# REUN_468349_001_PSU_Board_Power.net
KiCad netlist of a schematic drawn in Altium Designer
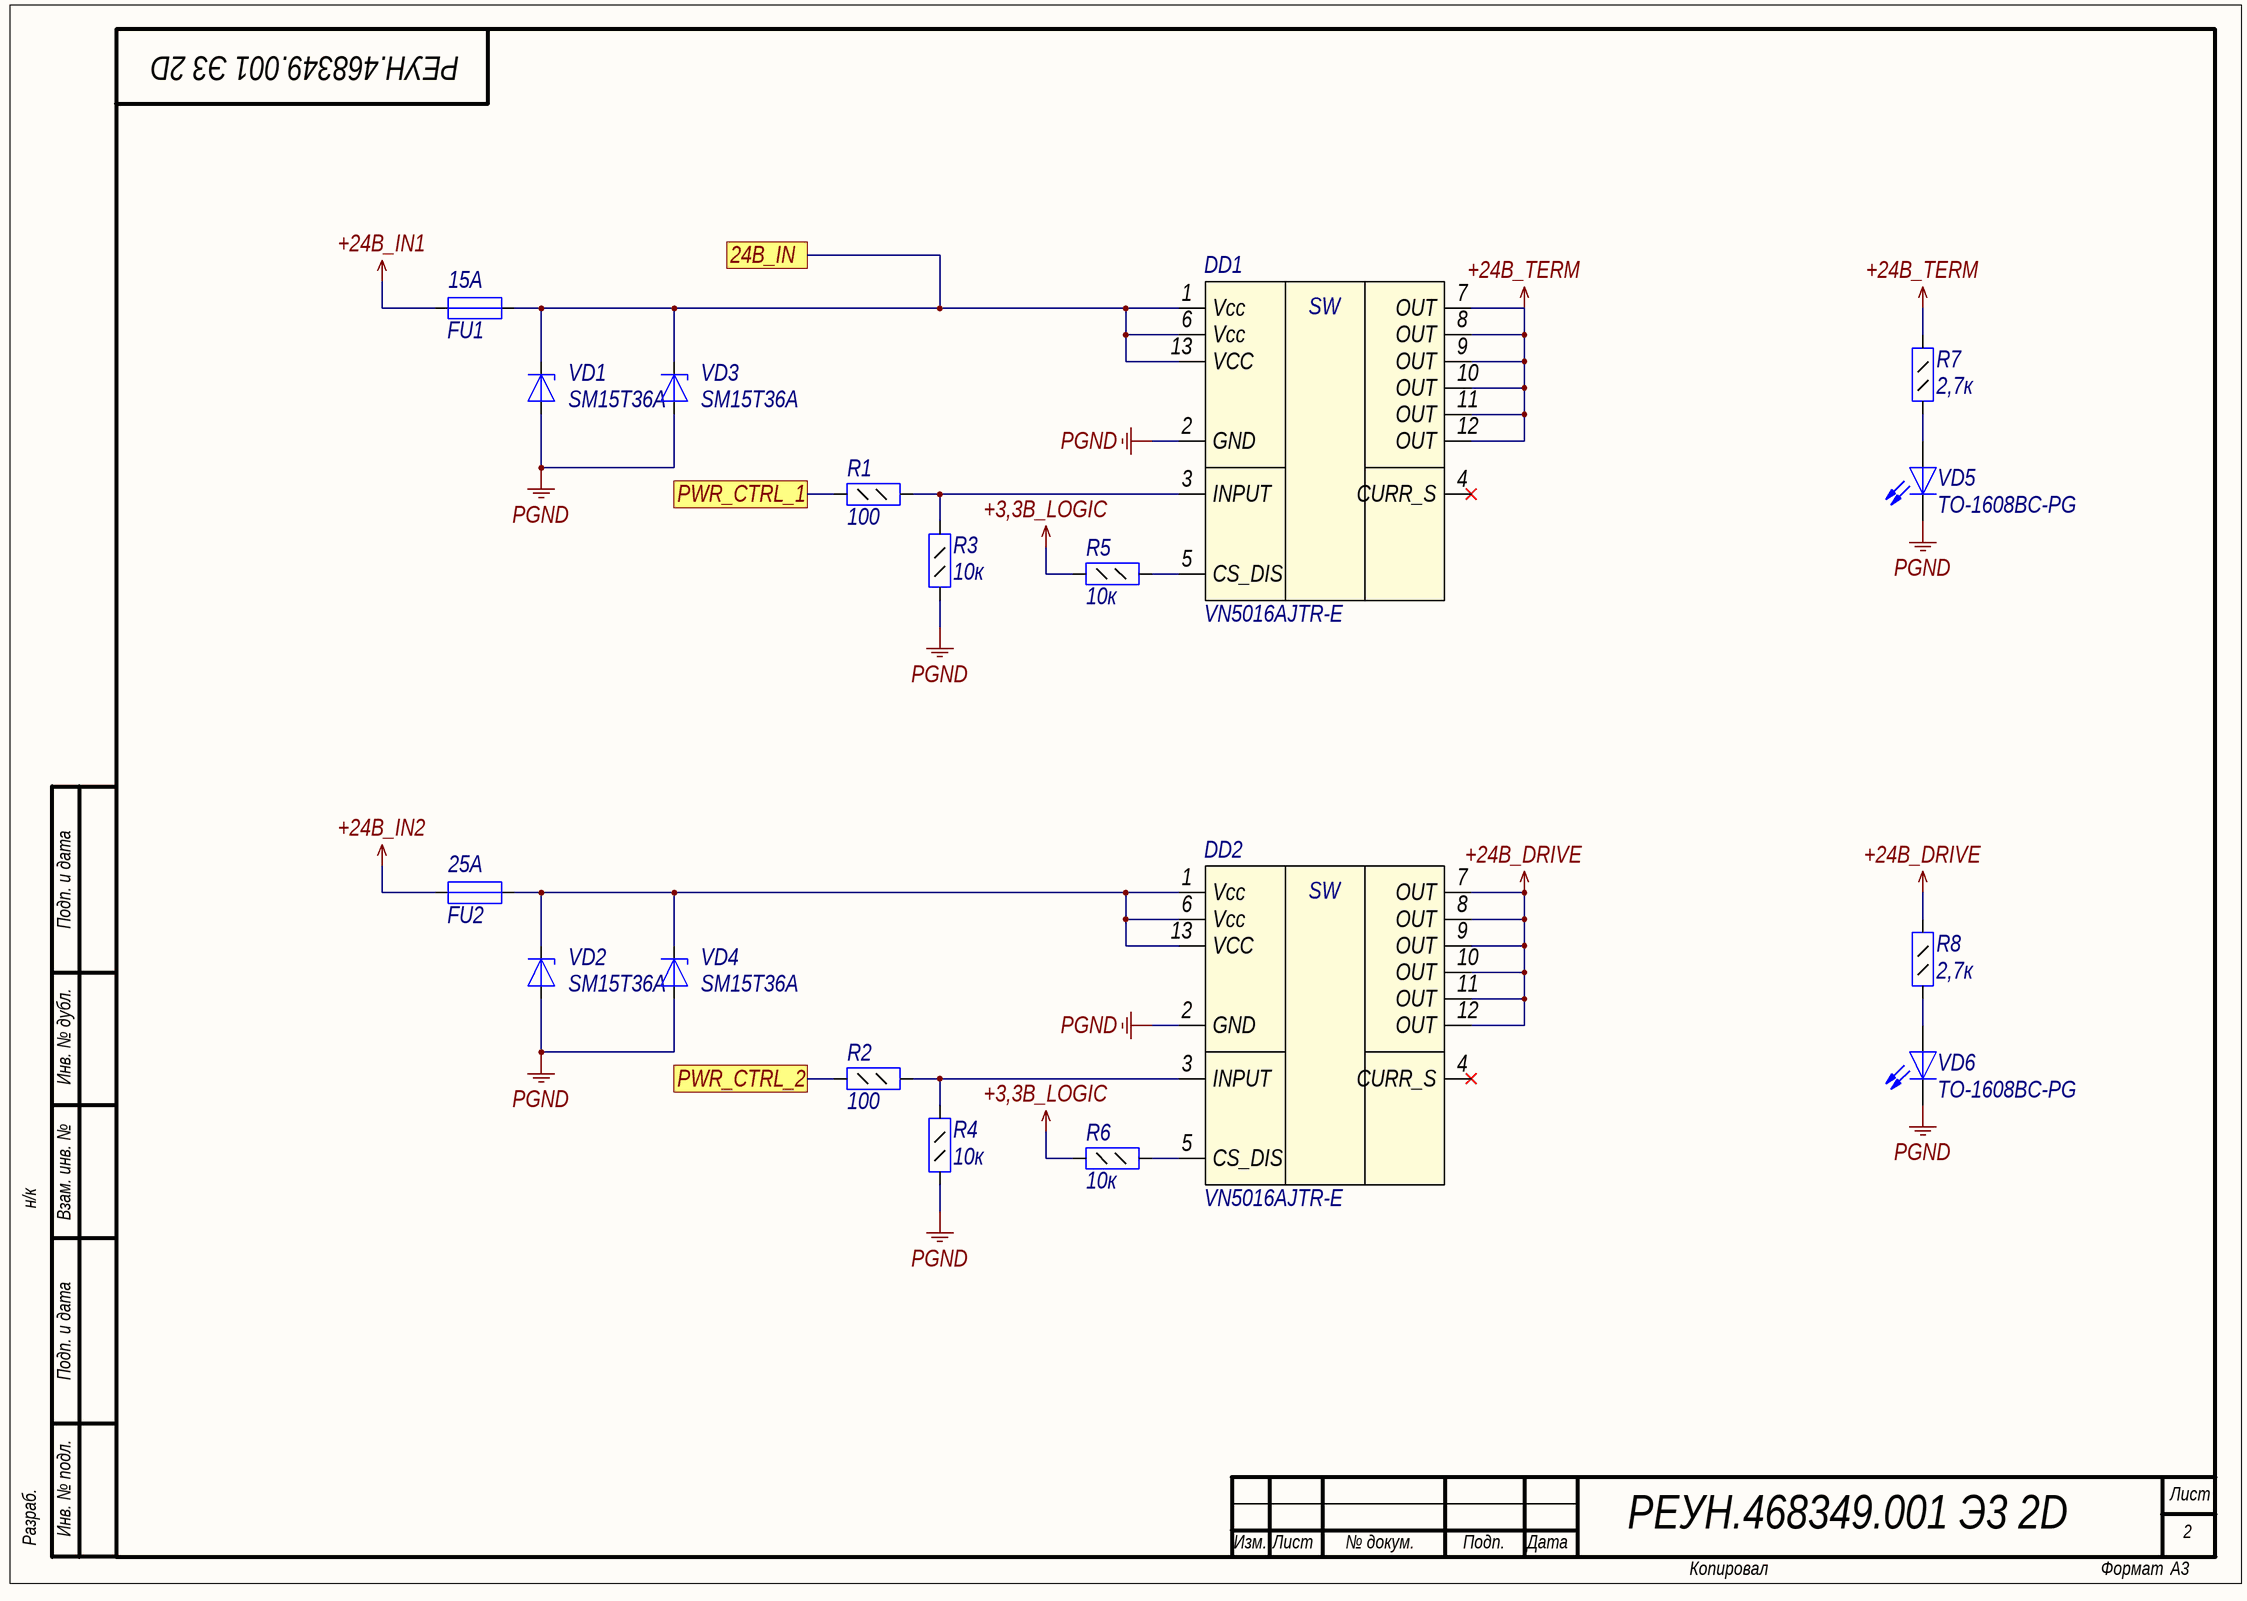
[diagram p0: REUN.468349.001_PSU_Board_Power.SchDoc]

(export (version "E")
  (design (tool "Eeschema 10.0.6"))
  (components
    (comp (ref "DD1")
      (value "VN5016AJTR-E")
      (footprint "POWERSO12")
      (description "Single channel high side driver with analog\r\ncurrent sense for automotive applications")
      (fields (field (name "MANUFACTURER") "STMicroelectronics"))
      (libsource (lib "REUN.468349.001_PSU_Board") (part "pwrsw5"))
    )
    (comp (ref "DD2")
      (value "VN5016AJTR-E")
      (footprint "POWERSO12")
      (description "Single channel high side driver with analog\r\ncurrent sense for automotive applications")
      (fields (field (name "MANUFACTURER") "STMicroelectronics"))
      (libsource (lib "REUN.468349.001_PSU_Board") (part "pwrsw5"))
    )
    (comp (ref "FU1")
      (value "Fuse")
      (footprint "F6.3x32")
      (description "Предохранитель")
      (fields (field (name "I MAX") "15А") (field (name "PART NUMBER") "189000.15"))
      (libsource (lib "MOP44") (part "Fuse"))
    )
    (comp (ref "FU2")
      (value "Fuse")
      (footprint "F6.3x30")
      (description "Предохранитель")
      (fields (field (name "I MAX") "25A") (field (name "PART NUMBER") "KLS5-1046-25000"))
      (libsource (lib "MOP44") (part "Fuse"))
    )
    (comp (ref "R1")
      (value "100")
      (footprint "R0805")
      (description "Резистор")
      (fields (field (name "PART NUMBER") "RC0805FR-07100RL") (field (name "POWER") "0,125Вт"))
      (libsource (lib "") (part "Resistor_0,125Вт_1"))
    )
    (comp (ref "R2")
      (value "100")
      (footprint "R0805")
      (description "Резистор")
      (fields (field (name "PART NUMBER") "RC0805FR-07100RL") (field (name "POWER") "0,125Вт"))
      (libsource (lib "") (part "Resistor_0,125Вт_1"))
    )
    (comp (ref "R3")
      (value "10к")
      (footprint "R0805")
      (description "Резистор")
      (fields (field (name "PART NUMBER") "RC0805FR-0710KL") (field (name "POWER") "0,125Вт"))
      (libsource (lib "MOP44") (part "Resistor_0,125Вт"))
    )
    (comp (ref "R4")
      (value "10к")
      (footprint "R0805")
      (description "Резистор")
      (fields (field (name "PART NUMBER") "RC0805FR-0710KL") (field (name "POWER") "0,125Вт"))
      (libsource (lib "MOP44") (part "Resistor_0,125Вт"))
    )
    (comp (ref "R5")
      (value "10к")
      (footprint "R0805")
      (description "Резистор")
      (fields (field (name "PART NUMBER") "RC0805FR-0710KL") (field (name "POWER") "0,125Вт"))
      (libsource (lib "") (part "Resistor_0,125Вт_1"))
    )
    (comp (ref "R6")
      (value "10к")
      (footprint "R0805")
      (description "Резистор")
      (fields (field (name "PART NUMBER") "RC0805FR-0710KL") (field (name "POWER") "0,125Вт"))
      (libsource (lib "") (part "Resistor_0,125Вт_1"))
    )
    (comp (ref "R7")
      (value "2,7к")
      (footprint "R0805")
      (description "Резистор")
      (fields (field (name "PART NUMBER") "RC0805FR-072K7") (field (name "POWER") "0,125Вт"))
      (libsource (lib "MOP44") (part "Resistor_0,125Вт"))
    )
    (comp (ref "R8")
      (value "2,7к")
      (footprint "R0805")
      (description "Резистор")
      (fields (field (name "PART NUMBER") "RC0805FR-072K7") (field (name "POWER") "0,125Вт"))
      (libsource (lib "MOP44") (part "Resistor_0,125Вт"))
    )
    (comp (ref "VD1")
      (value "SM15T36A")
      (footprint "SMC")
      (description "Cтабилитрон (лавинный выпрямительный диод) односторонний")
      (libsource (lib "MOP44") (part "DiodeZener"))
    )
    (comp (ref "VD2")
      (value "SM15T36A")
      (footprint "SMC")
      (description "Cтабилитрон (лавинный выпрямительный диод) односторонний")
      (libsource (lib "MOP44") (part "DiodeZener"))
    )
    (comp (ref "VD3")
      (value "SM15T36A")
      (footprint "SMC")
      (description "Cтабилитрон (лавинный выпрямительный диод) односторонний")
      (libsource (lib "MOP44") (part "DiodeZener"))
    )
    (comp (ref "VD4")
      (value "SM15T36A")
      (footprint "SMC")
      (description "Cтабилитрон (лавинный выпрямительный диод) односторонний")
      (libsource (lib "MOP44") (part "DiodeZener"))
    )
    (comp (ref "VD5")
      (value "TO-1608BC-PG")
      (footprint "L_0603_GREEN")
      (description "Светодиод")
      (libsource (lib "MOP44") (part "LED"))
    )
    (comp (ref "VD6")
      (value "TO-1608BC-PG")
      (footprint "L_0603_GREEN")
      (description "Светодиод")
      (libsource (lib "MOP44") (part "LED"))
    )
  )
  (nets
    (net (code "1") (name "+3,3B_LOGIC") (class "Default")
      (node (ref "R5") (pin "1") (pinfunction "1_1") (pintype "passive"))
      (node (ref "R6") (pin "1") (pinfunction "1_1") (pintype "passive"))
    )
    (net (code "2") (name "+24B_DRIVE") (class "Default")
      (node (ref "DD2") (pin "10") (pinfunction "OUT_10") (pintype "power_in"))
      (node (ref "DD2") (pin "11") (pinfunction "OUT_11") (pintype "power_in"))
      (node (ref "DD2") (pin "12") (pinfunction "OUT_12") (pintype "power_in"))
      (node (ref "DD2") (pin "7") (pinfunction "OUT_7") (pintype "power_in"))
      (node (ref "DD2") (pin "8") (pinfunction "OUT_8") (pintype "power_in"))
      (node (ref "DD2") (pin "9") (pinfunction "OUT_9") (pintype "power_in"))
      (node (ref "R8") (pin "2") (pinfunction "2_2") (pintype "passive"))
    )
    (net (code "3") (name "+24B_IN1") (class "Default")
      (node (ref "FU1") (pin "1") (pinfunction "1_1") (pintype "passive"))
    )
    (net (code "4") (name "+24B_IN2") (class "Default")
      (node (ref "FU2") (pin "1") (pinfunction "1_1") (pintype "passive"))
    )
    (net (code "5") (name "+24B_TERM") (class "Default")
      (node (ref "DD1") (pin "10") (pinfunction "OUT_10") (pintype "power_in"))
      (node (ref "DD1") (pin "11") (pinfunction "OUT_11") (pintype "power_in"))
      (node (ref "DD1") (pin "12") (pinfunction "OUT_12") (pintype "power_in"))
      (node (ref "DD1") (pin "7") (pinfunction "OUT_7") (pintype "power_in"))
      (node (ref "DD1") (pin "8") (pinfunction "OUT_8") (pintype "power_in"))
      (node (ref "DD1") (pin "9") (pinfunction "OUT_9") (pintype "power_in"))
      (node (ref "R7") (pin "2") (pinfunction "2_2") (pintype "passive"))
    )
    (net (code "6") (name "/24B_IN") (class "Default")
      (node (ref "DD1") (pin "1") (pinfunction "Vcc_1") (pintype "power_in"))
      (node (ref "DD1") (pin "13") (pinfunction "VCC_13") (pintype "power_in"))
      (node (ref "DD1") (pin "6") (pinfunction "Vcc_6") (pintype "power_in"))
      (node (ref "FU1") (pin "2") (pinfunction "2_2") (pintype "passive"))
      (node (ref "VD1") (pin "1") (pinfunction "K_1") (pintype "passive"))
      (node (ref "VD3") (pin "1") (pinfunction "K_1") (pintype "passive"))
    )
    (net (code "7") (name "/PWR_CTRL_1") (class "Default")
      (node (ref "R1") (pin "1") (pinfunction "1_1") (pintype "passive"))
    )
    (net (code "8") (name "/PWR_CTRL_2") (class "Default")
      (node (ref "R2") (pin "1") (pinfunction "1_1") (pintype "passive"))
    )
    (net (code "9") (name "Net-(DD1-CS_DIS)") (class "Default")
      (node (ref "DD1") (pin "5") (pinfunction "CS_DIS_5") (pintype "power_in"))
      (node (ref "R5") (pin "2") (pinfunction "2_2") (pintype "passive"))
    )
    (net (code "10") (name "Net-(DD1-INPUT)") (class "Default")
      (node (ref "DD1") (pin "3") (pinfunction "INPUT_3") (pintype "power_in"))
      (node (ref "R1") (pin "2") (pinfunction "2_2") (pintype "passive"))
      (node (ref "R3") (pin "2") (pinfunction "2_2") (pintype "passive"))
    )
    (net (code "11") (name "Net-(DD2-CS_DIS)") (class "Default")
      (node (ref "DD2") (pin "5") (pinfunction "CS_DIS_5") (pintype "power_in"))
      (node (ref "R6") (pin "2") (pinfunction "2_2") (pintype "passive"))
    )
    (net (code "12") (name "Net-(DD2-INPUT)") (class "Default")
      (node (ref "DD2") (pin "3") (pinfunction "INPUT_3") (pintype "power_in"))
      (node (ref "R2") (pin "2") (pinfunction "2_2") (pintype "passive"))
      (node (ref "R4") (pin "2") (pinfunction "2_2") (pintype "passive"))
    )
    (net (code "13") (name "Net-(DD2-VCC)") (class "Default")
      (node (ref "DD2") (pin "1") (pinfunction "Vcc_1") (pintype "power_in"))
      (node (ref "DD2") (pin "13") (pinfunction "VCC_13") (pintype "power_in"))
      (node (ref "DD2") (pin "6") (pinfunction "Vcc_6") (pintype "power_in"))
      (node (ref "FU2") (pin "2") (pinfunction "2_2") (pintype "passive"))
      (node (ref "VD2") (pin "1") (pinfunction "K_1") (pintype "passive"))
      (node (ref "VD4") (pin "1") (pinfunction "K_1") (pintype "passive"))
    )
    (net (code "14") (name "Net-(VD5-A)") (class "Default")
      (node (ref "R7") (pin "1") (pinfunction "1_1") (pintype "passive"))
      (node (ref "VD5") (pin "2") (pinfunction "A_2") (pintype "passive"))
    )
    (net (code "15") (name "Net-(VD6-A)") (class "Default")
      (node (ref "R8") (pin "1") (pinfunction "1_1") (pintype "passive"))
      (node (ref "VD6") (pin "2") (pinfunction "A_2") (pintype "passive"))
    )
    (net (code "16") (name "PGND") (class "Default")
      (node (ref "DD1") (pin "2") (pinfunction "GND_2") (pintype "power_in"))
      (node (ref "DD2") (pin "2") (pinfunction "GND_2") (pintype "power_in"))
      (node (ref "R3") (pin "1") (pinfunction "1_1") (pintype "passive"))
      (node (ref "R4") (pin "1") (pinfunction "1_1") (pintype "passive"))
      (node (ref "VD1") (pin "2") (pinfunction "A_2") (pintype "passive"))
      (node (ref "VD2") (pin "2") (pinfunction "A_2") (pintype "passive"))
      (node (ref "VD3") (pin "2") (pinfunction "A_2") (pintype "passive"))
      (node (ref "VD4") (pin "2") (pinfunction "A_2") (pintype "passive"))
      (node (ref "VD5") (pin "1") (pinfunction "K_1") (pintype "passive"))
      (node (ref "VD6") (pin "1") (pinfunction "K_1") (pintype "passive"))
    )
    (net (code "17") (name "unconnected-(DD1-CURR_S-Pad4)") (class "Default")
      (node (ref "DD1") (pin "4") (pinfunction "CURR_S_4") (pintype "power_in+no_connect"))
    )
    (net (code "18") (name "unconnected-(DD2-CURR_S-Pad4)") (class "Default")
      (node (ref "DD2") (pin "4") (pinfunction "CURR_S_4") (pintype "power_in+no_connect"))
    )
  )
)
